# driverV1_0.net
KiCad netlist of a schematic drawn in Altium Designer
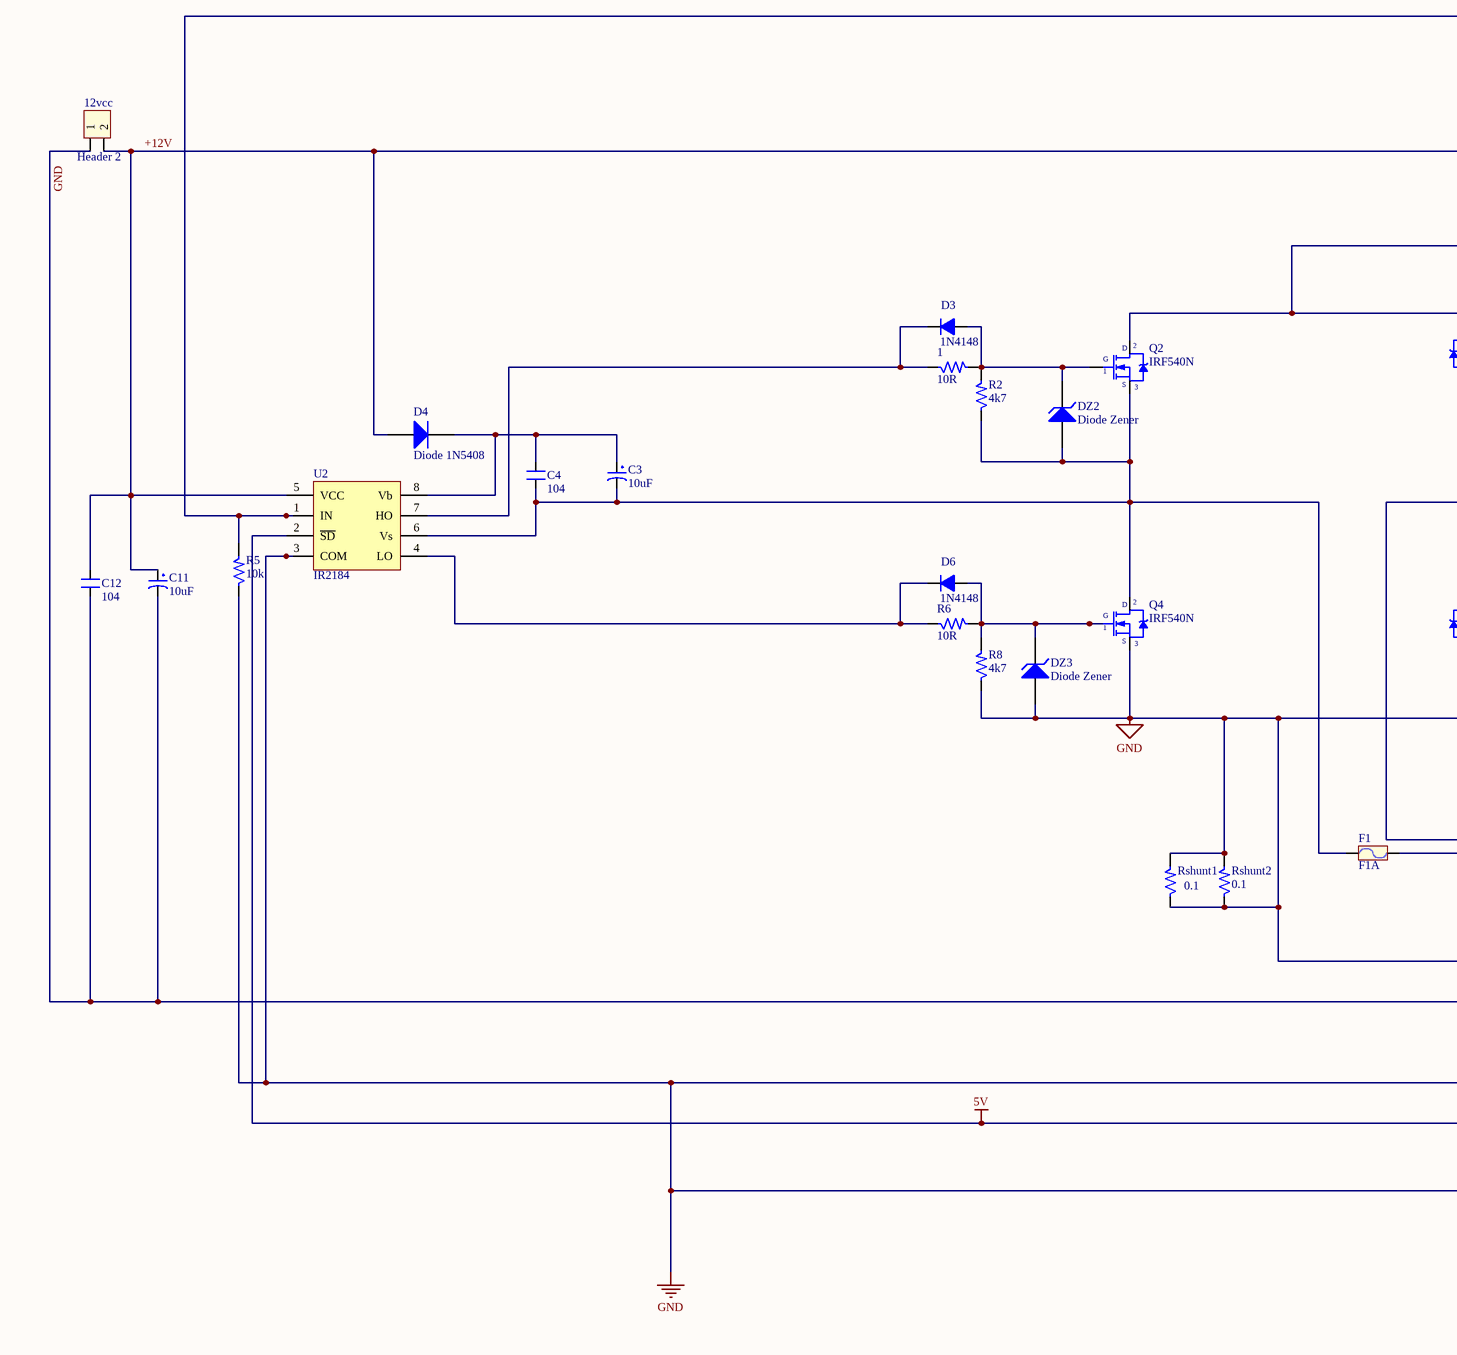
[diagram p0: driverV1.0.SchDoc, left]
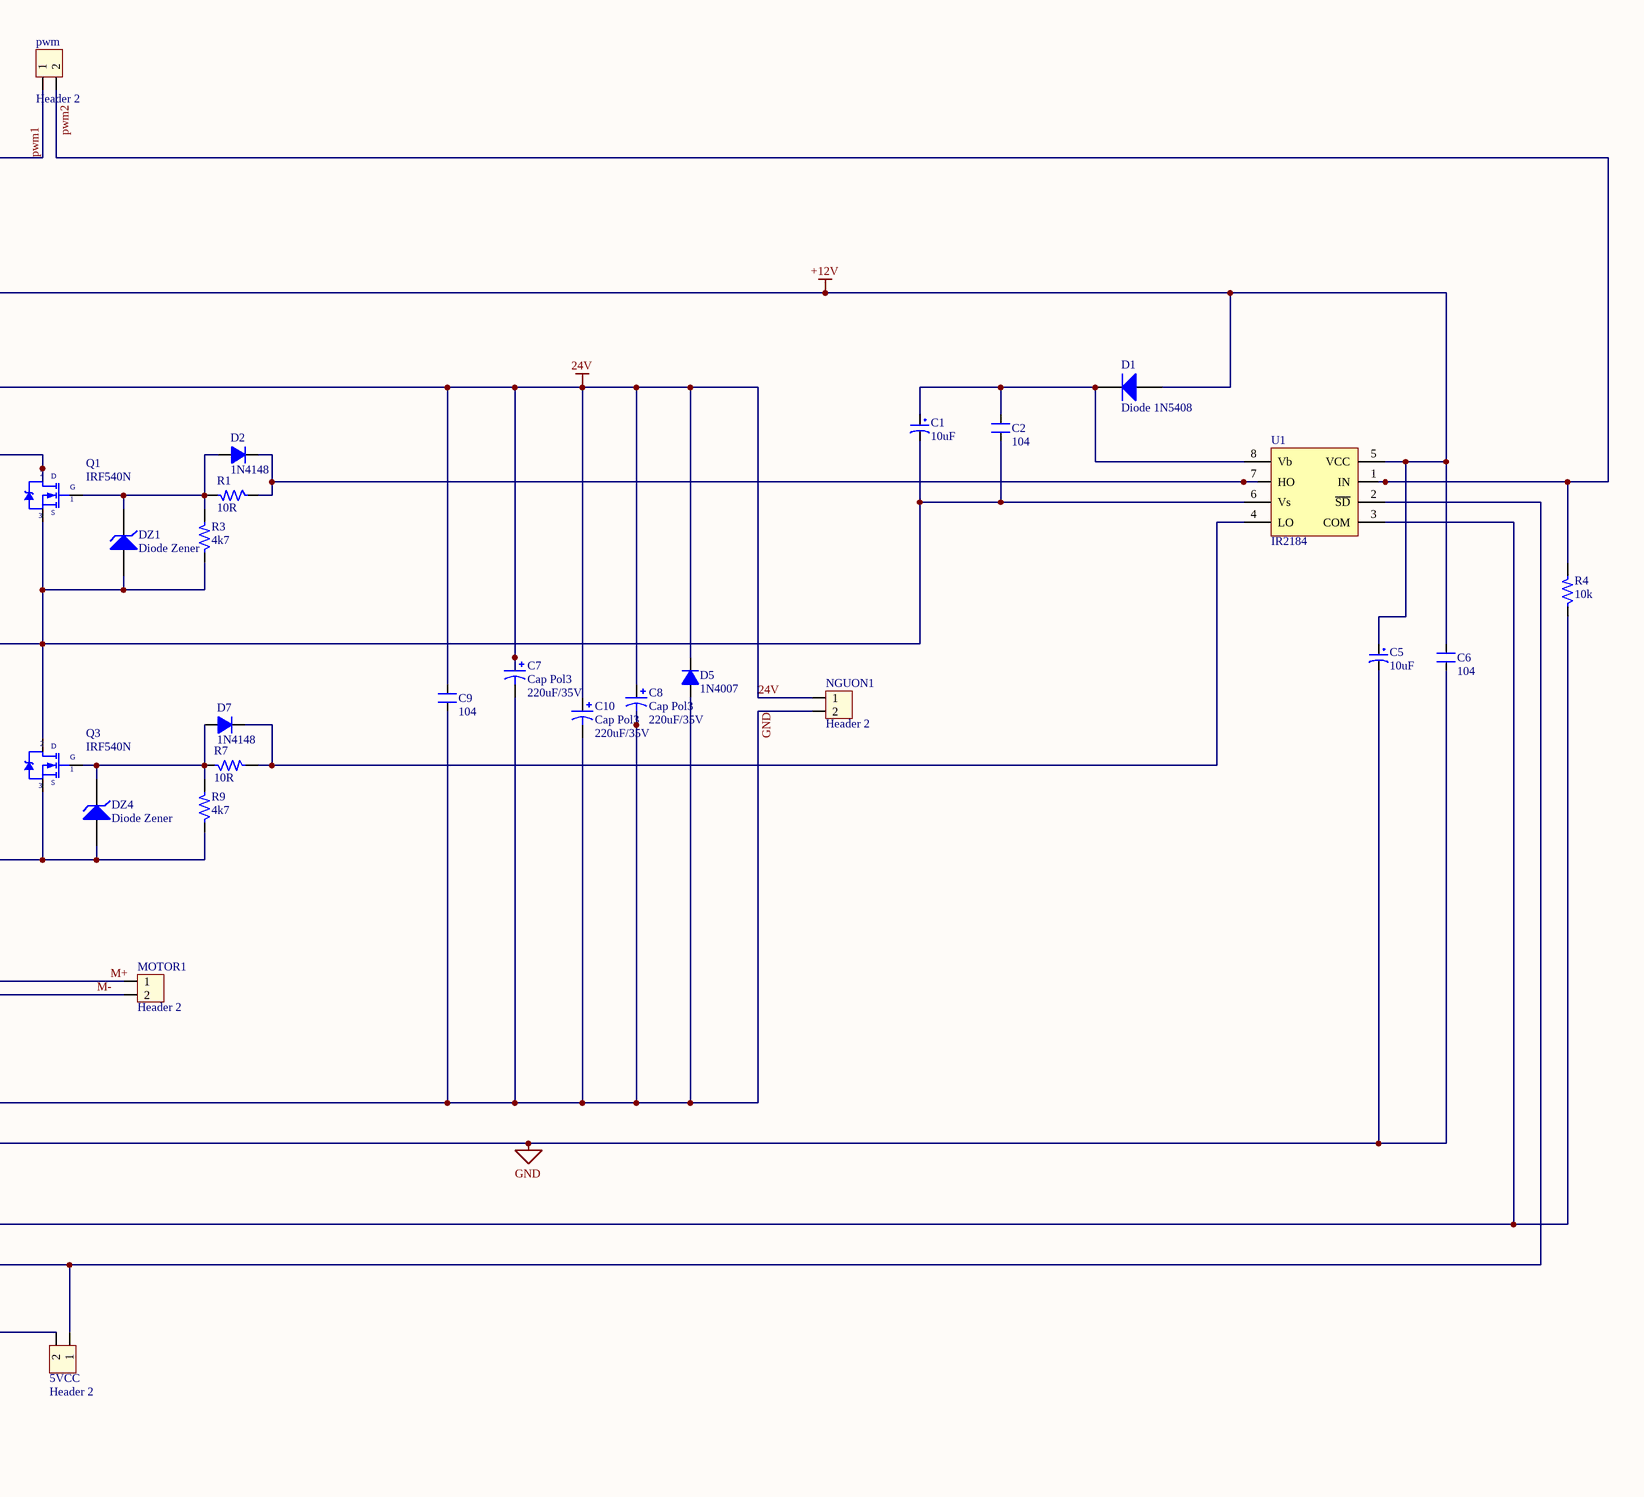
[diagram p1: driverV1.0.SchDoc, right]

(export (version "E")
  (design (tool "Eeschema 10.0.6"))
  (components
    (comp (ref "1")
      (value "10R")
      (footprint "SM-1206")
      (description "Resistor 1/4W")
      (libsource (lib "syhaunguyen") (part "R"))
    )
    (comp (ref "5VCC")
      (value "Header 2")
      (footprint "HED2")
      (description "Header 2 (Green)")
      (libsource (lib "") (part "Hed2_1"))
    )
    (comp (ref "12vcc")
      (value "Header 2")
      (footprint "HED2")
      (description "Header 2 (Green)")
      (libsource (lib "syhaunguyen") (part "Hed2"))
    )
    (comp (ref "C1")
      (value "10uF")
      (footprint "CP1/2")
      (description "Cap P  0,1uF < 22uF , 16 - 50V")
      (libsource (lib "syhaunguyen") (part "CP1"))
    )
    (comp (ref "C2")
      (value "104")
      (footprint "SM-0805")
      (description "Cap SMD")
      (libsource (lib "My Library") (part "CM"))
    )
    (comp (ref "C3")
      (value "10uF")
      (footprint "CP1/2")
      (description "Cap P  0,1uF < 22uF , 16 - 50V")
      (libsource (lib "syhaunguyen") (part "CP1"))
    )
    (comp (ref "C4")
      (value "104")
      (footprint "SM-0805")
      (description "Cap SMD")
      (libsource (lib "My Library") (part "CM"))
    )
    (comp (ref "C5")
      (value "10uF")
      (footprint "CP1/2")
      (description "Cap P  0,1uF < 22uF , 16 - 50V")
      (libsource (lib "syhaunguyen") (part "CP1"))
    )
    (comp (ref "C6")
      (value "104")
      (footprint "SM-0805")
      (description "Cap SMD")
      (libsource (lib "My Library") (part "CM"))
    )
    (comp (ref "C7")
      (value "Cap Pol3")
      (footprint "CP2/5")
      (description "Polarized Capacitor (Surface Mount)")
      (fields (field (name "ALTIUM_VALUE") "220uF/35V") (field (name "PUBLISHER") "Altium Limited"))
      (libsource (lib "syhaunguyen") (part "Cap Pol3"))
    )
    (comp (ref "C8")
      (value "Cap Pol3")
      (footprint "CP2/5")
      (description "Polarized Capacitor (Surface Mount)")
      (fields (field (name "ALTIUM_VALUE") "220uF/35V") (field (name "PUBLISHER") "Altium Limited"))
      (libsource (lib "syhaunguyen") (part "Cap Pol3"))
    )
    (comp (ref "C9")
      (value "104")
      (footprint "SM-0805")
      (description "Cap SMD")
      (libsource (lib "My Library") (part "CM"))
    )
    (comp (ref "C10")
      (value "Cap Pol3")
      (footprint "CP2/5")
      (description "Polarized Capacitor (Surface Mount)")
      (fields (field (name "ALTIUM_VALUE") "220uF/35V") (field (name "PUBLISHER") "Altium Limited"))
      (libsource (lib "syhaunguyen") (part "Cap Pol3"))
    )
    (comp (ref "C11")
      (value "10uF")
      (footprint "CP1/2")
      (description "Cap P  0,1uF < 22uF , 16 - 50V")
      (libsource (lib "syhaunguyen") (part "CP1"))
    )
    (comp (ref "C12")
      (value "104")
      (footprint "SM-0805")
      (description "Cap SMD")
      (libsource (lib "My Library") (part "CM"))
    )
    (comp (ref "D1")
      (value "Diode 1N5408")
      (footprint "DO-201AD")
      (description "3 Amp Medium Power Silicon Rectifier Diode")
      (fields (field (name "PUBLISHER") "Altium Limited"))
      (libsource (lib "Miscellaneous Devices") (part "Diode 1N5408"))
    )
    (comp (ref "D2")
      (value "1N4148")
      (footprint "D1A")
      (description "Diode 1A")
      (libsource (lib "syhaunguyen") (part "D1A"))
    )
    (comp (ref "D3")
      (value "1N4148")
      (footprint "D1A")
      (description "Diode 1A")
      (libsource (lib "syhaunguyen") (part "D1A"))
    )
    (comp (ref "D4")
      (value "Diode 1N5408")
      (footprint "DO-201AD")
      (description "3 Amp Medium Power Silicon Rectifier Diode")
      (fields (field (name "PUBLISHER") "Altium Limited"))
      (libsource (lib "Miscellaneous Devices") (part "Diode 1N5408"))
    )
    (comp (ref "D5")
      (value "1N4007")
      (footprint "D1A")
      (description "Diode 1A")
      (libsource (lib "My Library") (part "D1A"))
    )
    (comp (ref "D6")
      (value "1N4148")
      (footprint "D1A")
      (description "Diode 1A")
      (libsource (lib "syhaunguyen") (part "D1A"))
    )
    (comp (ref "D7")
      (value "1N4148")
      (footprint "D1A")
      (description "Diode 1A")
      (libsource (lib "syhaunguyen") (part "D1A"))
    )
    (comp (ref "DZ1")
      (value "Diode Zener")
      (footprint "DIODE/NOM/0.5A")
      (description "Zener Diode")
      (fields (field (name "PUBLISHER") "Altium Limited"))
      (libsource (lib "Schematic") (part "Diode Zener"))
    )
    (comp (ref "DZ2")
      (value "Diode Zener")
      (footprint "DIODE/NOM/0.5A")
      (description "Zener Diode")
      (fields (field (name "PUBLISHER") "Altium Limited"))
      (libsource (lib "Schematic") (part "Diode Zener"))
    )
    (comp (ref "DZ3")
      (value "Diode Zener")
      (footprint "DIODE/NOM/0.5A")
      (description "Zener Diode")
      (fields (field (name "PUBLISHER") "Altium Limited"))
      (libsource (lib "Schematic") (part "Diode Zener"))
    )
    (comp (ref "DZ4")
      (value "Diode Zener")
      (footprint "DIODE/NOM/0.5A")
      (description "Zener Diode")
      (fields (field (name "PUBLISHER") "Altium Limited"))
      (libsource (lib "Schematic") (part "Diode Zener"))
    )
    (comp (ref "F1")
      (value "F1A")
      (footprint "Fuse")
      (description "Fuse")
      (fields (field (name "DESIGNED BY") "VanDungEvn"))
      (libsource (lib "syhaunguyen") (part "Fuse"))
    )
    (comp (ref "MOTOR1")
      (value "Header 2")
      (footprint "HED2")
      (description "Header 2 (Green)")
      (libsource (lib "My Library") (part "Hed2"))
    )
    (comp (ref "NGUON1")
      (value "Header 2")
      (footprint "HED2")
      (description "Header 2 (Green)")
      (libsource (lib "My Library") (part "Hed2"))
    )
    (comp (ref "pwm")
      (value "Header 2")
      (footprint "HED2")
      (description "Header 2 (Green)")
      (libsource (lib "syhaunguyen") (part "Hed2"))
    )
    (comp (ref "Q1")
      (value "IRF540N")
      (footprint "QTO-220")
      (description "MOSFET N - CHANNEL 500V - 0.75 - 8A - TO-220")
      (libsource (lib "syhaunguyen") (part "IRF840"))
    )
    (comp (ref "Q2")
      (value "IRF540N")
      (footprint "QTO-220")
      (description "MOSFET N - CHANNEL 500V - 0.75 - 8A - TO-220")
      (libsource (lib "syhaunguyen") (part "IRF840"))
    )
    (comp (ref "Q3")
      (value "IRF540N")
      (footprint "QTO-220")
      (description "MOSFET N - CHANNEL 500V - 0.75 - 8A - TO-220")
      (libsource (lib "syhaunguyen") (part "IRF840"))
    )
    (comp (ref "Q4")
      (value "IRF540N")
      (footprint "QTO-220")
      (description "MOSFET N - CHANNEL 500V - 0.75 - 8A - TO-220")
      (libsource (lib "syhaunguyen") (part "IRF840"))
    )
    (comp (ref "R1")
      (value "10R")
      (footprint "SM-1206")
      (description "Resistor 1/4W")
      (libsource (lib "syhaunguyen") (part "R"))
    )
    (comp (ref "R2")
      (value "4k7")
      (footprint "SM-1206")
      (description "Resistor 1/4W")
      (libsource (lib "syhaunguyen") (part "R"))
    )
    (comp (ref "R3")
      (value "4k7")
      (footprint "SM-1206")
      (description "Resistor 1/4W")
      (libsource (lib "syhaunguyen") (part "R"))
    )
    (comp (ref "R4")
      (value "10k")
      (footprint "SM-1206")
      (description "Resistor 1/4W")
      (libsource (lib "syhaunguyen") (part "R"))
    )
    (comp (ref "R5")
      (value "10k")
      (footprint "SM-1206")
      (description "Resistor 1/4W")
      (libsource (lib "syhaunguyen") (part "R"))
    )
    (comp (ref "R6")
      (value "10R")
      (footprint "SM-1206")
      (description "Resistor 1/4W")
      (libsource (lib "syhaunguyen") (part "R"))
    )
    (comp (ref "R7")
      (value "10R")
      (footprint "SM-1206")
      (description "Resistor 1/4W")
      (libsource (lib "syhaunguyen") (part "R"))
    )
    (comp (ref "R8")
      (value "4k7")
      (footprint "SM-1206")
      (description "Resistor 1/4W")
      (libsource (lib "syhaunguyen") (part "R"))
    )
    (comp (ref "R9")
      (value "4k7")
      (footprint "SM-1206")
      (description "Resistor 1/4W")
      (libsource (lib "syhaunguyen") (part "R"))
    )
    (comp (ref "Rshunt1")
      (value "0.1")
      (footprint "SM-1206")
      (description "Resistor 1/4W")
      (libsource (lib "syhaunguyen") (part "R"))
    )
    (comp (ref "Rshunt2")
      (value "0.1")
      (footprint "SM-1206")
      (description "Resistor 1/4W")
      (libsource (lib "syhaunguyen") (part "R"))
    )
    (comp (ref "U1")
      (value "IR2184")
      (footprint "SOIC127P490X600X175-8N")
      (description "Half-Bridge Driver")
      (libsource (lib "") (part "IR2184_1"))
    )
    (comp (ref "U2")
      (value "IR2184")
      (footprint "SOIC127P490X600X175-8N")
      (description "Half-Bridge Driver")
      (libsource (lib "syhaunguyen") (part "IR2184"))
    )
  )
  (nets
    (net (code "1") (name "+12V") (class "Default")
      (node (ref "12vcc") (pin "2") (pinfunction "2_2") (pintype "passive"))
      (node (ref "C11") (pin "1") (pinfunction "1_1") (pintype "passive"))
      (node (ref "C12") (pin "2") (pinfunction "2_2") (pintype "passive"))
      (node (ref "C5") (pin "1") (pinfunction "1_1") (pintype "passive"))
      (node (ref "C6") (pin "2") (pinfunction "2_2") (pintype "passive"))
      (node (ref "D1") (pin "1") (pinfunction "A_1") (pintype "passive"))
      (node (ref "D4") (pin "1") (pinfunction "A_1") (pintype "passive"))
      (node (ref "U1") (pin "5") (pinfunction "VCC_5") (pintype "passive"))
      (node (ref "U2") (pin "5") (pinfunction "VCC_5") (pintype "passive"))
    )
    (net (code "2") (name "/M+") (class "Default")
      (node (ref "C1") (pin "2") (pinfunction "2_2") (pintype "passive"))
      (node (ref "C2") (pin "1") (pinfunction "1_1") (pintype "passive"))
      (node (ref "DZ1") (pin "1") (pinfunction "A_1") (pintype "passive"))
      (node (ref "MOTOR1") (pin "1") (pinfunction "1_1") (pintype "passive"))
      (node (ref "Q1") (pin "3") (pinfunction "S_3") (pintype "passive"))
      (node (ref "Q3") (pin "2") (pinfunction "D_2") (pintype "passive"))
      (node (ref "R3") (pin "1") (pinfunction "1_1") (pintype "passive"))
      (node (ref "U1") (pin "6") (pinfunction "Vs_6") (pintype "passive"))
    )
    (net (code "3") (name "/M-") (class "Default")
      (node (ref "F1") (pin "2") (pinfunction "2_2") (pintype "passive"))
      (node (ref "MOTOR1") (pin "2") (pinfunction "2_2") (pintype "passive"))
    )
    (net (code "4") (name "/pwm1") (class "Default")
      (node (ref "R5") (pin "2") (pinfunction "2_2") (pintype "passive"))
      (node (ref "U2") (pin "1") (pinfunction "IN_1") (pintype "passive"))
      (node (ref "pwm") (pin "1") (pinfunction "1_1") (pintype "passive"))
    )
    (net (code "5") (name "/pwm2") (class "Default")
      (node (ref "R4") (pin "2") (pinfunction "2_2") (pintype "passive"))
      (node (ref "U1") (pin "1") (pinfunction "IN_1") (pintype "passive"))
      (node (ref "pwm") (pin "2") (pinfunction "2_2") (pintype "passive"))
    )
    (net (code "6") (name "5V") (class "Default")
      (node (ref "5VCC") (pin "1") (pinfunction "1_1") (pintype "passive"))
      (node (ref "U1") (pin "2") (pinfunction "~{SD}_2") (pintype "passive"))
      (node (ref "U2") (pin "2") (pinfunction "~{SD}_2") (pintype "passive"))
    )
    (net (code "7") (name "24V") (class "Default")
      (node (ref "C10") (pin "1") (pinfunction "1_1") (pintype "passive"))
      (node (ref "C7") (pin "1") (pinfunction "1_1") (pintype "passive"))
      (node (ref "C8") (pin "1") (pinfunction "1_1") (pintype "passive"))
      (node (ref "C9") (pin "2") (pinfunction "2_2") (pintype "passive"))
      (node (ref "D5") (pin "2") (pinfunction "K_2") (pintype "passive"))
      (node (ref "NGUON1") (pin "1") (pinfunction "1_1") (pintype "passive"))
      (node (ref "Q1") (pin "2") (pinfunction "D_2") (pintype "passive"))
      (node (ref "Q2") (pin "2") (pinfunction "D_2") (pintype "passive"))
    )
    (net (code "8") (name "GND") (class "Default")
      (node (ref "12vcc") (pin "1") (pinfunction "1_1") (pintype "passive"))
      (node (ref "5VCC") (pin "2") (pinfunction "2_2") (pintype "passive"))
      (node (ref "C10") (pin "2") (pinfunction "2_2") (pintype "passive"))
      (node (ref "C11") (pin "2") (pinfunction "2_2") (pintype "passive"))
      (node (ref "C12") (pin "1") (pinfunction "1_1") (pintype "passive"))
      (node (ref "C5") (pin "2") (pinfunction "2_2") (pintype "passive"))
      (node (ref "C6") (pin "1") (pinfunction "1_1") (pintype "passive"))
      (node (ref "C7") (pin "2") (pinfunction "2_2") (pintype "passive"))
      (node (ref "C8") (pin "2") (pinfunction "2_2") (pintype "passive"))
      (node (ref "C9") (pin "1") (pinfunction "1_1") (pintype "passive"))
      (node (ref "D5") (pin "1") (pinfunction "A_1") (pintype "passive"))
      (node (ref "DZ3") (pin "1") (pinfunction "A_1") (pintype "passive"))
      (node (ref "DZ4") (pin "1") (pinfunction "A_1") (pintype "passive"))
      (node (ref "NGUON1") (pin "2") (pinfunction "2_2") (pintype "passive"))
      (node (ref "Q3") (pin "3") (pinfunction "S_3") (pintype "passive"))
      (node (ref "Q4") (pin "3") (pinfunction "S_3") (pintype "passive"))
      (node (ref "R4") (pin "1") (pinfunction "1_1") (pintype "passive"))
      (node (ref "R5") (pin "1") (pinfunction "1_1") (pintype "passive"))
      (node (ref "R8") (pin "1") (pinfunction "1_1") (pintype "passive"))
      (node (ref "R9") (pin "1") (pinfunction "1_1") (pintype "passive"))
      (node (ref "Rshunt1") (pin "1") (pinfunction "1_1") (pintype "passive"))
      (node (ref "Rshunt1") (pin "2") (pinfunction "2_2") (pintype "passive"))
      (node (ref "Rshunt2") (pin "1") (pinfunction "1_1") (pintype "passive"))
      (node (ref "Rshunt2") (pin "2") (pinfunction "2_2") (pintype "passive"))
      (node (ref "U1") (pin "3") (pinfunction "COM_3") (pintype "passive"))
      (node (ref "U2") (pin "3") (pinfunction "COM_3") (pintype "passive"))
    )
    (net (code "9") (name "Net-(D1-K)") (class "Default")
      (node (ref "C1") (pin "1") (pinfunction "1_1") (pintype "passive"))
      (node (ref "C2") (pin "2") (pinfunction "2_2") (pintype "passive"))
      (node (ref "D1") (pin "2") (pinfunction "K_2") (pintype "passive"))
      (node (ref "U1") (pin "8") (pinfunction "Vb_8") (pintype "passive"))
    )
    (net (code "10") (name "Net-(D2-A)") (class "Default")
      (node (ref "D2") (pin "1") (pinfunction "A_1") (pintype "passive"))
      (node (ref "DZ1") (pin "2") (pinfunction "K_2") (pintype "passive"))
      (node (ref "Q1") (pin "1") (pinfunction "G_1") (pintype "passive"))
      (node (ref "R1") (pin "2") (pinfunction "2_2") (pintype "passive"))
      (node (ref "R3") (pin "2") (pinfunction "2_2") (pintype "passive"))
    )
    (net (code "11") (name "Net-(D2-K)") (class "Default")
      (node (ref "D2") (pin "2") (pinfunction "K_2") (pintype "passive"))
      (node (ref "R1") (pin "1") (pinfunction "1_1") (pintype "passive"))
      (node (ref "U1") (pin "7") (pinfunction "HO_7") (pintype "passive"))
    )
    (net (code "12") (name "Net-(D3-A)") (class "Default")
      (node (ref "1") (pin "2") (pinfunction "2_2") (pintype "passive"))
      (node (ref "D3") (pin "1") (pinfunction "A_1") (pintype "passive"))
      (node (ref "DZ2") (pin "2") (pinfunction "K_2") (pintype "passive"))
      (node (ref "Q2") (pin "1") (pinfunction "G_1") (pintype "passive"))
      (node (ref "R2") (pin "2") (pinfunction "2_2") (pintype "passive"))
    )
    (net (code "13") (name "Net-(D3-K)") (class "Default")
      (node (ref "1") (pin "1") (pinfunction "1_1") (pintype "passive"))
      (node (ref "D3") (pin "2") (pinfunction "K_2") (pintype "passive"))
      (node (ref "U2") (pin "7") (pinfunction "HO_7") (pintype "passive"))
    )
    (net (code "14") (name "Net-(D4-K)") (class "Default")
      (node (ref "C3") (pin "1") (pinfunction "1_1") (pintype "passive"))
      (node (ref "C4") (pin "2") (pinfunction "2_2") (pintype "passive"))
      (node (ref "D4") (pin "2") (pinfunction "K_2") (pintype "passive"))
      (node (ref "U2") (pin "8") (pinfunction "Vb_8") (pintype "passive"))
    )
    (net (code "15") (name "Net-(D6-A)") (class "Default")
      (node (ref "D6") (pin "1") (pinfunction "A_1") (pintype "passive"))
      (node (ref "DZ3") (pin "2") (pinfunction "K_2") (pintype "passive"))
      (node (ref "Q4") (pin "1") (pinfunction "G_1") (pintype "passive"))
      (node (ref "R6") (pin "2") (pinfunction "2_2") (pintype "passive"))
      (node (ref "R8") (pin "2") (pinfunction "2_2") (pintype "passive"))
    )
    (net (code "16") (name "Net-(D6-K)") (class "Default")
      (node (ref "D6") (pin "2") (pinfunction "K_2") (pintype "passive"))
      (node (ref "R6") (pin "1") (pinfunction "1_1") (pintype "passive"))
      (node (ref "U2") (pin "4") (pinfunction "LO_4") (pintype "passive"))
    )
    (net (code "17") (name "Net-(D7-A)") (class "Default")
      (node (ref "D7") (pin "1") (pinfunction "A_1") (pintype "passive"))
      (node (ref "DZ4") (pin "2") (pinfunction "K_2") (pintype "passive"))
      (node (ref "Q3") (pin "1") (pinfunction "G_1") (pintype "passive"))
      (node (ref "R7") (pin "1") (pinfunction "1_1") (pintype "passive"))
      (node (ref "R9") (pin "2") (pinfunction "2_2") (pintype "passive"))
    )
    (net (code "18") (name "Net-(D7-K)") (class "Default")
      (node (ref "D7") (pin "2") (pinfunction "K_2") (pintype "passive"))
      (node (ref "R7") (pin "2") (pinfunction "2_2") (pintype "passive"))
      (node (ref "U1") (pin "4") (pinfunction "LO_4") (pintype "passive"))
    )
    (net (code "19") (name "Net-(DZ2-A)") (class "Default")
      (node (ref "C3") (pin "2") (pinfunction "2_2") (pintype "passive"))
      (node (ref "C4") (pin "1") (pinfunction "1_1") (pintype "passive"))
      (node (ref "DZ2") (pin "1") (pinfunction "A_1") (pintype "passive"))
      (node (ref "F1") (pin "1") (pinfunction "1_1") (pintype "passive"))
      (node (ref "Q2") (pin "3") (pinfunction "S_3") (pintype "passive"))
      (node (ref "Q4") (pin "2") (pinfunction "D_2") (pintype "passive"))
      (node (ref "R2") (pin "1") (pinfunction "1_1") (pintype "passive"))
      (node (ref "U2") (pin "6") (pinfunction "Vs_6") (pintype "passive"))
    )
  )
)
